# fotodiodo.net
KiCad netlist of a schematic drawn in EAGLE
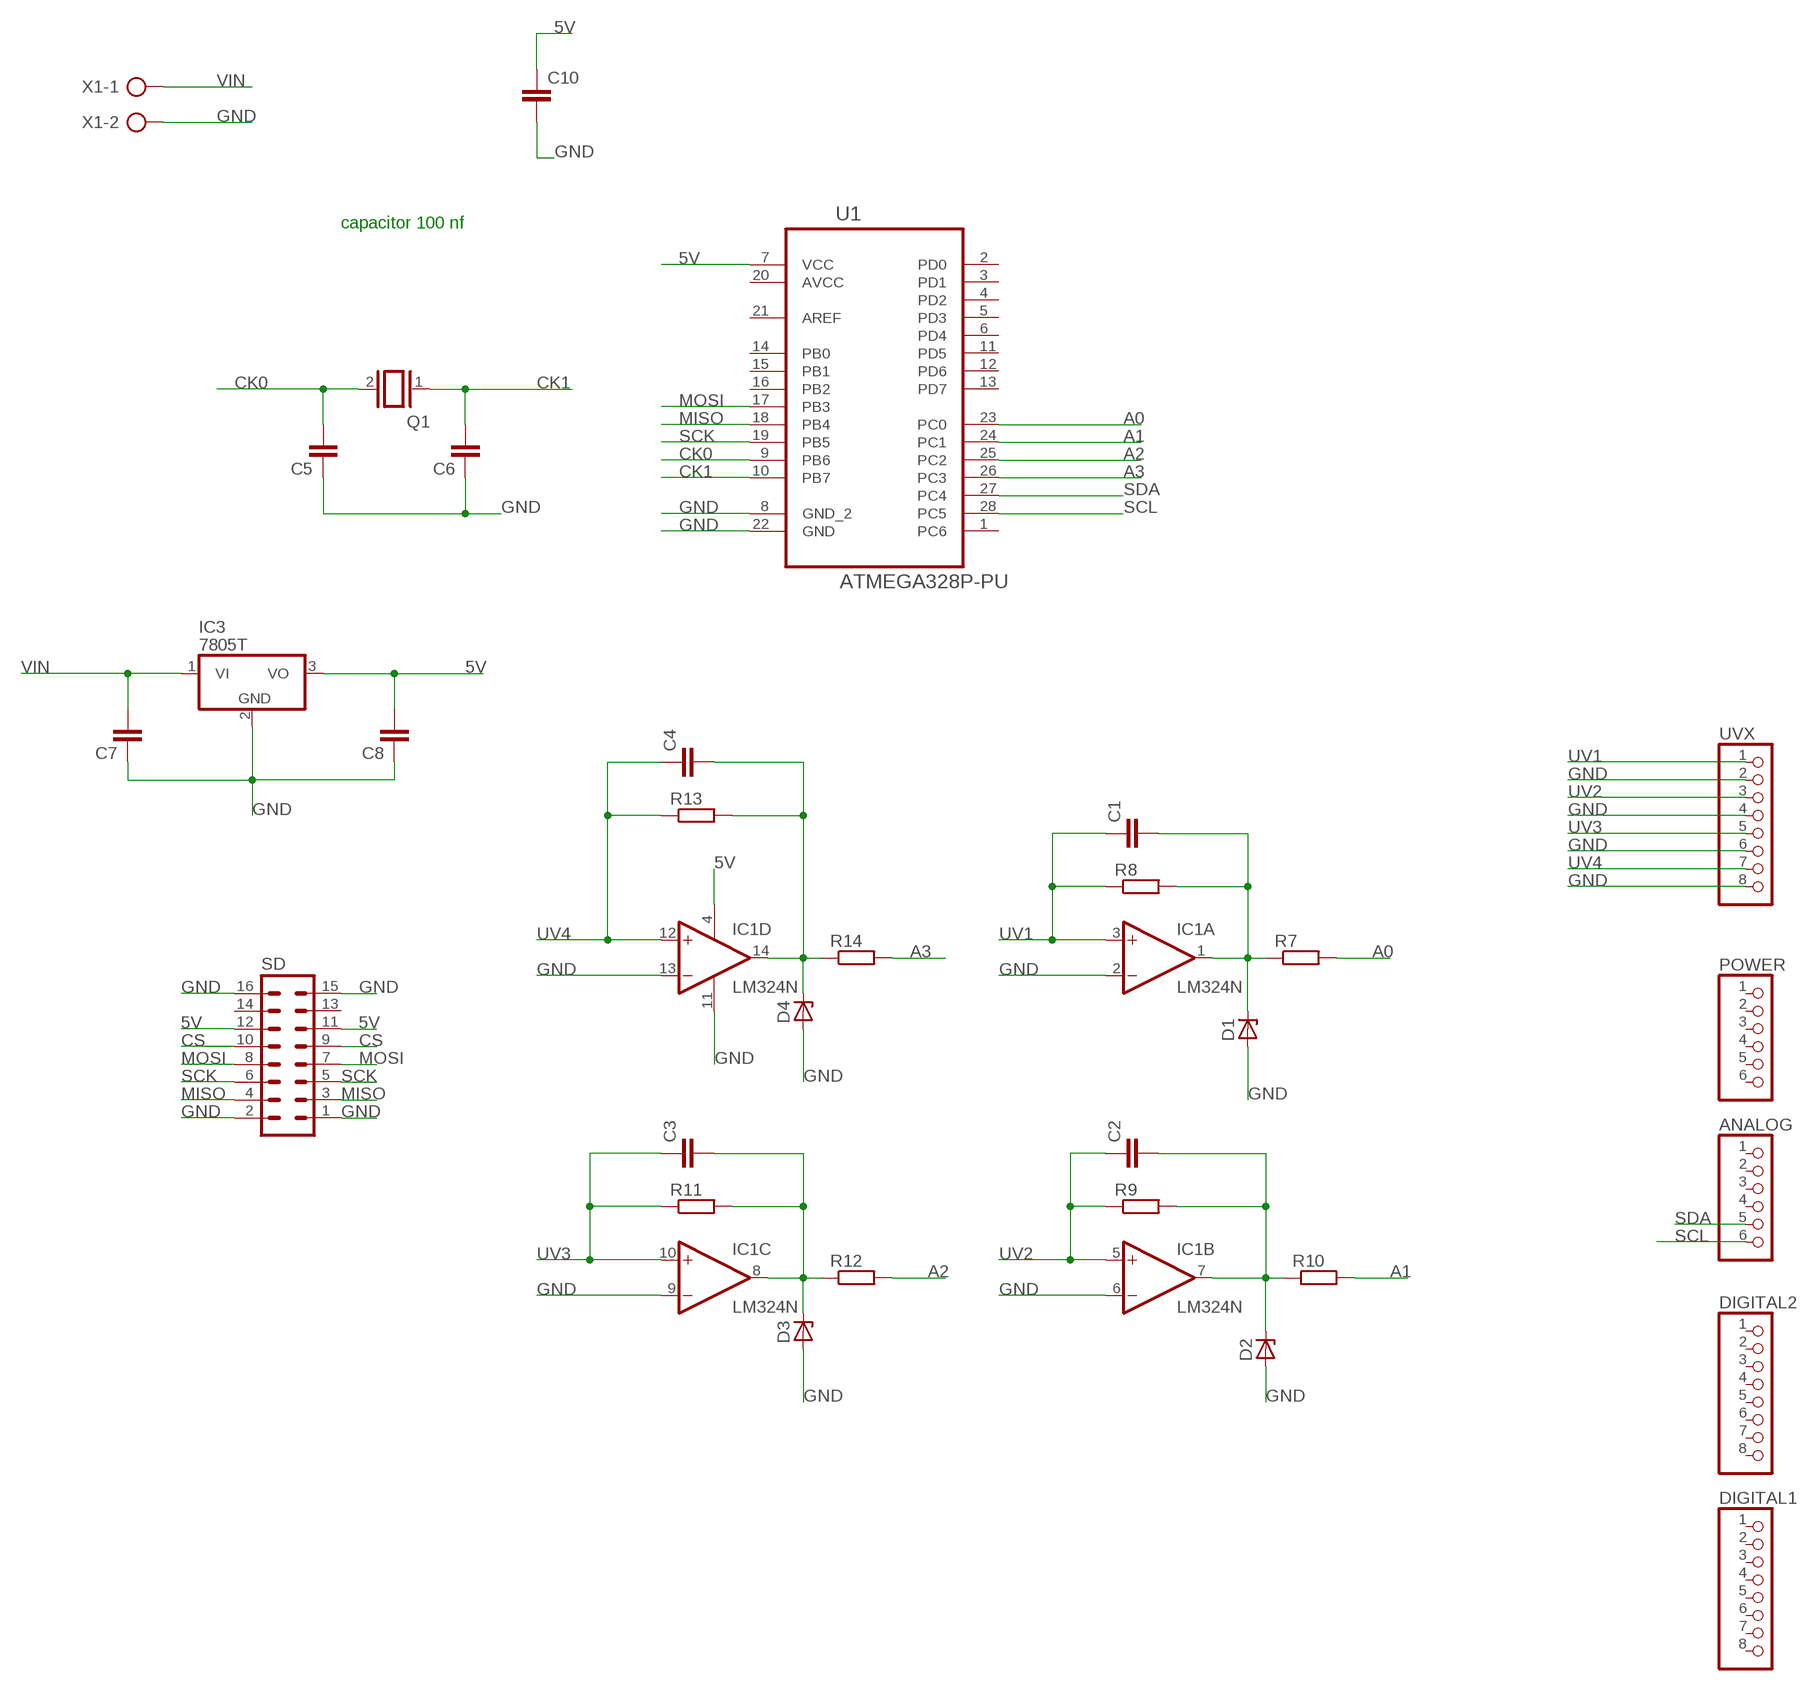
[diagram p0: schematic, sheet 1]

(export (version "E")
  (design (tool "Eeschema 10.0.6"))
  (components
    (comp (ref "ANALOG")
      (value "PINHD-1X6")
      (footprint "eagle-import:1X06")
      (libsource (lib "eagle-import") (part "PINHD-1X6"))
    )
    (comp (ref "C1")
      (value "C-EU025-025X050")
      (footprint "eagle-import:C025-025X050")
      (libsource (lib "eagle-import") (part "C-EU025-025X050"))
    )
    (comp (ref "C2")
      (value "C-EU025-025X050")
      (footprint "eagle-import:C025-025X050")
      (libsource (lib "eagle-import") (part "C-EU025-025X050"))
    )
    (comp (ref "C3")
      (value "C-EU025-025X050")
      (footprint "eagle-import:C025-025X050")
      (libsource (lib "eagle-import") (part "C-EU025-025X050"))
    )
    (comp (ref "C4")
      (value "C-EU025-025X050")
      (footprint "eagle-import:C025-025X050")
      (libsource (lib "eagle-import") (part "C-EU025-025X050"))
    )
    (comp (ref "C5")
      (value "C-EU025-025X050")
      (footprint "eagle-import:C025-025X050")
      (libsource (lib "eagle-import") (part "C-EU025-025X050"))
    )
    (comp (ref "C6")
      (value "C-EU025-025X050")
      (footprint "eagle-import:C025-025X050")
      (libsource (lib "eagle-import") (part "C-EU025-025X050"))
    )
    (comp (ref "C7")
      (value "C-EU025-025X050")
      (footprint "eagle-import:C025-025X050")
      (libsource (lib "eagle-import") (part "C-EU025-025X050"))
    )
    (comp (ref "C8")
      (value "C-EU025-025X050")
      (footprint "eagle-import:C025-025X050")
      (libsource (lib "eagle-import") (part "C-EU025-025X050"))
    )
    (comp (ref "C10")
      (value "C-EU050-055X075")
      (footprint "eagle-import:C050-055X075")
      (libsource (lib "eagle-import") (part "resistor_C-EU050-055X075"))
    )
    (comp (ref "D1")
      (value "ZENER-DIODEC1702-15")
      (footprint "eagle-import:C1702-15")
      (libsource (lib "eagle-import") (part "ZENER-DIODEC1702-15"))
    )
    (comp (ref "D2")
      (value "ZENER-DIODEC1702-15")
      (footprint "eagle-import:C1702-15")
      (libsource (lib "eagle-import") (part "ZENER-DIODEC1702-15"))
    )
    (comp (ref "D3")
      (value "ZENER-DIODEC1702-15")
      (footprint "eagle-import:C1702-15")
      (libsource (lib "eagle-import") (part "ZENER-DIODEC1702-15"))
    )
    (comp (ref "D4")
      (value "ZENER-DIODEC1702-15")
      (footprint "eagle-import:C1702-15")
      (libsource (lib "eagle-import") (part "ZENER-DIODEC1702-15"))
    )
    (comp (ref "DIGITAL1")
      (value "PINHD-1X8")
      (footprint "eagle-import:1X08")
      (libsource (lib "eagle-import") (part "PINHD-1X8"))
    )
    (comp (ref "DIGITAL2")
      (value "PINHD-1X8")
      (footprint "eagle-import:1X08")
      (libsource (lib "eagle-import") (part "PINHD-1X8"))
    )
    (comp (ref "IC1")
      (value "LM324N")
      (footprint "eagle-import:DIL14")
      (libsource (lib "eagle-import") (part "LM324N"))
    )
    (comp (ref "IC3")
      (value "7805T")
      (footprint "eagle-import:TO220H")
      (libsource (lib "eagle-import") (part "78T05"))
    )
    (comp (ref "POWER")
      (value "PINHD-1X6")
      (footprint "eagle-import:1X06")
      (libsource (lib "eagle-import") (part "PINHD-1X6"))
    )
    (comp (ref "Q1")
      (value "XTAL/S")
      (footprint "eagle-import:QS")
      (libsource (lib "eagle-import") (part "XTAL/S"))
    )
    (comp (ref "R7")
      (value "R-EU_0207/10")
      (footprint "eagle-import:0207_10")
      (libsource (lib "eagle-import") (part "R-EU_0207/10"))
    )
    (comp (ref "R8")
      (value "R-EU_0207/10")
      (footprint "eagle-import:0207_10")
      (libsource (lib "eagle-import") (part "R-EU_0207/10"))
    )
    (comp (ref "R9")
      (value "R-EU_0207/10")
      (footprint "eagle-import:0207_10")
      (libsource (lib "eagle-import") (part "R-EU_0207/10"))
    )
    (comp (ref "R10")
      (value "R-EU_0207/10")
      (footprint "eagle-import:0207_10")
      (libsource (lib "eagle-import") (part "R-EU_0207/10"))
    )
    (comp (ref "R11")
      (value "R-EU_0207/10")
      (footprint "eagle-import:0207_10")
      (libsource (lib "eagle-import") (part "R-EU_0207/10"))
    )
    (comp (ref "R12")
      (value "R-EU_0207/10")
      (footprint "eagle-import:0207_10")
      (libsource (lib "eagle-import") (part "R-EU_0207/10"))
    )
    (comp (ref "R13")
      (value "R-EU_0207/10")
      (footprint "eagle-import:0207_10")
      (libsource (lib "eagle-import") (part "R-EU_0207/10"))
    )
    (comp (ref "R14")
      (value "R-EU_0207/10")
      (footprint "eagle-import:0207_10")
      (libsource (lib "eagle-import") (part "R-EU_0207/10"))
    )
    (comp (ref "SD")
      (value "MA08-2")
      (footprint "eagle-import:MA08-2")
      (libsource (lib "eagle-import") (part "MA08-2"))
    )
    (comp (ref "U1")
      (value "ATMEGA328P-PU")
      (footprint "eagle-import:DIP254P762X457-28")
      (libsource (lib "eagle-import") (part "ATMEGA328P-PU"))
    )
    (comp (ref "UVX")
      (value "PINHD-1X8")
      (footprint "eagle-import:1X08")
      (libsource (lib "eagle-import") (part "PINHD-1X8"))
    )
    (comp (ref "X1")
      (value "AK500/2-H")
      (footprint "eagle-import:AK500_2-H")
      (libsource (lib "eagle-import") (part "AK500/2-H"))
    )
  )
  (nets
    (net (code "1") (name "/5V") (class "Default")
      (node (ref "C10") (pin "1") (pinfunction "1_1") (pintype "passive"))
      (node (ref "C8") (pin "2") (pinfunction "2_2") (pintype "passive"))
      (node (ref "IC1") (pin "4") (pinfunction "V+_4") (pintype "power_in"))
      (node (ref "IC3") (pin "3") (pinfunction "VO_3") (pintype "passive"))
      (node (ref "SD") (pin "11") (pinfunction "11_11") (pintype "passive"))
      (node (ref "SD") (pin "12") (pinfunction "12_12") (pintype "passive"))
      (node (ref "U1") (pin "7") (pinfunction "VCC_7") (pintype "power_in"))
    )
    (net (code "2") (name "/A0") (class "Default")
      (node (ref "R7") (pin "2") (pinfunction "2_2") (pintype "passive"))
      (node (ref "U1") (pin "23") (pinfunction "PC0_23") (pintype "bidirectional"))
    )
    (net (code "3") (name "/A1") (class "Default")
      (node (ref "R10") (pin "2") (pinfunction "2_2") (pintype "passive"))
      (node (ref "U1") (pin "24") (pinfunction "PC1_24") (pintype "bidirectional"))
    )
    (net (code "4") (name "/A2") (class "Default")
      (node (ref "R12") (pin "2") (pinfunction "2_2") (pintype "passive"))
      (node (ref "U1") (pin "25") (pinfunction "PC2_25") (pintype "bidirectional"))
    )
    (net (code "5") (name "/A3") (class "Default")
      (node (ref "R14") (pin "2") (pinfunction "2_2") (pintype "passive"))
      (node (ref "U1") (pin "26") (pinfunction "PC3_26") (pintype "bidirectional"))
    )
    (net (code "6") (name "/AVCC") (class "Default")
      (node (ref "U1") (pin "20") (pinfunction "AVCC_20") (pintype "power_in"))
    )
    (net (code "7") (name "/CK0") (class "Default")
      (node (ref "C5") (pin "2") (pinfunction "2_2") (pintype "passive"))
      (node (ref "Q1") (pin "2") (pinfunction "2_2") (pintype "passive"))
      (node (ref "U1") (pin "9") (pinfunction "PB6_9") (pintype "bidirectional"))
    )
    (net (code "8") (name "/CK1") (class "Default")
      (node (ref "C6") (pin "2") (pinfunction "2_2") (pintype "passive"))
      (node (ref "Q1") (pin "1") (pinfunction "1_1") (pintype "passive"))
      (node (ref "U1") (pin "10") (pinfunction "PB7_10") (pintype "bidirectional"))
    )
    (net (code "9") (name "/CS") (class "Default")
      (node (ref "SD") (pin "10") (pinfunction "10_10") (pintype "passive"))
      (node (ref "SD") (pin "9") (pinfunction "9_9") (pintype "passive"))
    )
    (net (code "10") (name "/GND") (class "Default")
      (node (ref "C10") (pin "2") (pinfunction "2_2") (pintype "passive"))
      (node (ref "C5") (pin "1") (pinfunction "1_1") (pintype "passive"))
      (node (ref "C6") (pin "1") (pinfunction "1_1") (pintype "passive"))
      (node (ref "C7") (pin "1") (pinfunction "1_1") (pintype "passive"))
      (node (ref "C8") (pin "1") (pinfunction "1_1") (pintype "passive"))
      (node (ref "D1") (pin "A") (pinfunction "A_A") (pintype "passive"))
      (node (ref "D2") (pin "A") (pinfunction "A_A") (pintype "passive"))
      (node (ref "D3") (pin "A") (pinfunction "A_A") (pintype "passive"))
      (node (ref "D4") (pin "A") (pinfunction "A_A") (pintype "passive"))
      (node (ref "IC1") (pin "11") (pinfunction "V-_11") (pintype "power_in"))
      (node (ref "IC1") (pin "13") (pinfunction "-IN_13") (pintype "input"))
      (node (ref "IC1") (pin "2") (pinfunction "-IN_2") (pintype "input"))
      (node (ref "IC1") (pin "6") (pinfunction "-IN_6") (pintype "input"))
      (node (ref "IC1") (pin "9") (pinfunction "-IN_9") (pintype "input"))
      (node (ref "IC3") (pin "2") (pinfunction "GND_2") (pintype "passive"))
      (node (ref "SD") (pin "1") (pinfunction "1_1") (pintype "passive"))
      (node (ref "SD") (pin "15") (pinfunction "15_15") (pintype "passive"))
      (node (ref "SD") (pin "16") (pinfunction "16_16") (pintype "passive"))
      (node (ref "SD") (pin "2") (pinfunction "2_2") (pintype "passive"))
      (node (ref "U1") (pin "22") (pinfunction "GND_22") (pintype "passive"))
      (node (ref "U1") (pin "8") (pinfunction "GND_2_8") (pintype "passive"))
      (node (ref "UVX") (pin "2") (pinfunction "2_2") (pintype "passive"))
      (node (ref "UVX") (pin "4") (pinfunction "4_4") (pintype "passive"))
      (node (ref "UVX") (pin "6") (pinfunction "6_6") (pintype "passive"))
      (node (ref "UVX") (pin "8") (pinfunction "8_8") (pintype "passive"))
      (node (ref "X1") (pin "2") (pinfunction "KL_2") (pintype "passive"))
    )
    (net (code "11") (name "/MISO") (class "Default")
      (node (ref "SD") (pin "3") (pinfunction "3_3") (pintype "passive"))
      (node (ref "SD") (pin "4") (pinfunction "4_4") (pintype "passive"))
      (node (ref "U1") (pin "18") (pinfunction "PB4_18") (pintype "bidirectional"))
    )
    (net (code "12") (name "/MOSI") (class "Default")
      (node (ref "SD") (pin "7") (pinfunction "7_7") (pintype "passive"))
      (node (ref "SD") (pin "8") (pinfunction "8_8") (pintype "passive"))
      (node (ref "U1") (pin "17") (pinfunction "PB3_17") (pintype "bidirectional"))
    )
    (net (code "13") (name "/SCK") (class "Default")
      (node (ref "SD") (pin "5") (pinfunction "5_5") (pintype "passive"))
      (node (ref "SD") (pin "6") (pinfunction "6_6") (pintype "passive"))
      (node (ref "U1") (pin "19") (pinfunction "PB5_19") (pintype "bidirectional"))
    )
    (net (code "14") (name "/SCL") (class "Default")
      (node (ref "ANALOG") (pin "6") (pinfunction "6_6") (pintype "passive"))
      (node (ref "U1") (pin "28") (pinfunction "PC5_28") (pintype "bidirectional"))
    )
    (net (code "15") (name "/SDA") (class "Default")
      (node (ref "ANALOG") (pin "5") (pinfunction "5_5") (pintype "passive"))
      (node (ref "U1") (pin "27") (pinfunction "PC4_27") (pintype "bidirectional"))
    )
    (net (code "16") (name "/UV1") (class "Default")
      (node (ref "C1") (pin "1") (pinfunction "1_1") (pintype "passive"))
      (node (ref "IC1") (pin "3") (pinfunction "+IN_3") (pintype "input"))
      (node (ref "R8") (pin "1") (pinfunction "1_1") (pintype "passive"))
      (node (ref "UVX") (pin "1") (pinfunction "1_1") (pintype "passive"))
    )
    (net (code "17") (name "/UV2") (class "Default")
      (node (ref "C2") (pin "1") (pinfunction "1_1") (pintype "passive"))
      (node (ref "IC1") (pin "5") (pinfunction "+IN_5") (pintype "input"))
      (node (ref "R9") (pin "1") (pinfunction "1_1") (pintype "passive"))
      (node (ref "UVX") (pin "3") (pinfunction "3_3") (pintype "passive"))
    )
    (net (code "18") (name "/UV3") (class "Default")
      (node (ref "C3") (pin "1") (pinfunction "1_1") (pintype "passive"))
      (node (ref "IC1") (pin "10") (pinfunction "+IN_10") (pintype "input"))
      (node (ref "R11") (pin "1") (pinfunction "1_1") (pintype "passive"))
      (node (ref "UVX") (pin "5") (pinfunction "5_5") (pintype "passive"))
    )
    (net (code "19") (name "/UV4") (class "Default")
      (node (ref "C4") (pin "1") (pinfunction "1_1") (pintype "passive"))
      (node (ref "IC1") (pin "12") (pinfunction "+IN_12") (pintype "input"))
      (node (ref "R13") (pin "1") (pinfunction "1_1") (pintype "passive"))
      (node (ref "UVX") (pin "7") (pinfunction "7_7") (pintype "passive"))
    )
    (net (code "20") (name "/VIN") (class "Default")
      (node (ref "C7") (pin "2") (pinfunction "2_2") (pintype "passive"))
      (node (ref "IC3") (pin "1") (pinfunction "VI_1") (pintype "input"))
      (node (ref "X1") (pin "1") (pinfunction "KL_1") (pintype "passive"))
    )
    (net (code "21") (name "Net-(IC1A-OUT)") (class "Default")
      (node (ref "C1") (pin "2") (pinfunction "2_2") (pintype "passive"))
      (node (ref "D1") (pin "C") (pinfunction "C_C") (pintype "passive"))
      (node (ref "IC1") (pin "1") (pinfunction "OUT_1") (pintype "output"))
      (node (ref "R7") (pin "1") (pinfunction "1_1") (pintype "passive"))
      (node (ref "R8") (pin "2") (pinfunction "2_2") (pintype "passive"))
    )
    (net (code "22") (name "Net-(IC1B-OUT)") (class "Default")
      (node (ref "C2") (pin "2") (pinfunction "2_2") (pintype "passive"))
      (node (ref "D2") (pin "C") (pinfunction "C_C") (pintype "passive"))
      (node (ref "IC1") (pin "7") (pinfunction "OUT_7") (pintype "output"))
      (node (ref "R10") (pin "1") (pinfunction "1_1") (pintype "passive"))
      (node (ref "R9") (pin "2") (pinfunction "2_2") (pintype "passive"))
    )
    (net (code "23") (name "Net-(IC1C-OUT)") (class "Default")
      (node (ref "C3") (pin "2") (pinfunction "2_2") (pintype "passive"))
      (node (ref "D3") (pin "C") (pinfunction "C_C") (pintype "passive"))
      (node (ref "IC1") (pin "8") (pinfunction "OUT_8") (pintype "output"))
      (node (ref "R11") (pin "2") (pinfunction "2_2") (pintype "passive"))
      (node (ref "R12") (pin "1") (pinfunction "1_1") (pintype "passive"))
    )
    (net (code "24") (name "Net-(IC1D-OUT)") (class "Default")
      (node (ref "C4") (pin "2") (pinfunction "2_2") (pintype "passive"))
      (node (ref "D4") (pin "C") (pinfunction "C_C") (pintype "passive"))
      (node (ref "IC1") (pin "14") (pinfunction "OUT_14") (pintype "output"))
      (node (ref "R13") (pin "2") (pinfunction "2_2") (pintype "passive"))
      (node (ref "R14") (pin "1") (pinfunction "1_1") (pintype "passive"))
    )
    (net (code "25") (name "unconnected-(ANALOG-Pad1)") (class "Default")
      (node (ref "ANALOG") (pin "1") (pinfunction "1_1") (pintype "passive"))
    )
    (net (code "26") (name "unconnected-(ANALOG-Pad2)") (class "Default")
      (node (ref "ANALOG") (pin "2") (pinfunction "2_2") (pintype "passive"))
    )
    (net (code "27") (name "unconnected-(ANALOG-Pad3)") (class "Default")
      (node (ref "ANALOG") (pin "3") (pinfunction "3_3") (pintype "passive"))
    )
    (net (code "28") (name "unconnected-(ANALOG-Pad4)") (class "Default")
      (node (ref "ANALOG") (pin "4") (pinfunction "4_4") (pintype "passive"))
    )
    (net (code "29") (name "unconnected-(DIGITAL1-Pad1)") (class "Default")
      (node (ref "DIGITAL1") (pin "1") (pinfunction "1_1") (pintype "passive"))
    )
    (net (code "30") (name "unconnected-(DIGITAL1-Pad2)") (class "Default")
      (node (ref "DIGITAL1") (pin "2") (pinfunction "2_2") (pintype "passive"))
    )
    (net (code "31") (name "unconnected-(DIGITAL1-Pad3)") (class "Default")
      (node (ref "DIGITAL1") (pin "3") (pinfunction "3_3") (pintype "passive"))
    )
    (net (code "32") (name "unconnected-(DIGITAL1-Pad4)") (class "Default")
      (node (ref "DIGITAL1") (pin "4") (pinfunction "4_4") (pintype "passive"))
    )
    (net (code "33") (name "unconnected-(DIGITAL1-Pad5)") (class "Default")
      (node (ref "DIGITAL1") (pin "5") (pinfunction "5_5") (pintype "passive"))
    )
    (net (code "34") (name "unconnected-(DIGITAL1-Pad6)") (class "Default")
      (node (ref "DIGITAL1") (pin "6") (pinfunction "6_6") (pintype "passive"))
    )
    (net (code "35") (name "unconnected-(DIGITAL1-Pad7)") (class "Default")
      (node (ref "DIGITAL1") (pin "7") (pinfunction "7_7") (pintype "passive"))
    )
    (net (code "36") (name "unconnected-(DIGITAL1-Pad8)") (class "Default")
      (node (ref "DIGITAL1") (pin "8") (pinfunction "8_8") (pintype "passive"))
    )
    (net (code "37") (name "unconnected-(DIGITAL2-Pad1)") (class "Default")
      (node (ref "DIGITAL2") (pin "1") (pinfunction "1_1") (pintype "passive"))
    )
    (net (code "38") (name "unconnected-(DIGITAL2-Pad2)") (class "Default")
      (node (ref "DIGITAL2") (pin "2") (pinfunction "2_2") (pintype "passive"))
    )
    (net (code "39") (name "unconnected-(DIGITAL2-Pad3)") (class "Default")
      (node (ref "DIGITAL2") (pin "3") (pinfunction "3_3") (pintype "passive"))
    )
    (net (code "40") (name "unconnected-(DIGITAL2-Pad4)") (class "Default")
      (node (ref "DIGITAL2") (pin "4") (pinfunction "4_4") (pintype "passive"))
    )
    (net (code "41") (name "unconnected-(DIGITAL2-Pad5)") (class "Default")
      (node (ref "DIGITAL2") (pin "5") (pinfunction "5_5") (pintype "passive"))
    )
    (net (code "42") (name "unconnected-(DIGITAL2-Pad6)") (class "Default")
      (node (ref "DIGITAL2") (pin "6") (pinfunction "6_6") (pintype "passive"))
    )
    (net (code "43") (name "unconnected-(DIGITAL2-Pad7)") (class "Default")
      (node (ref "DIGITAL2") (pin "7") (pinfunction "7_7") (pintype "passive"))
    )
    (net (code "44") (name "unconnected-(DIGITAL2-Pad8)") (class "Default")
      (node (ref "DIGITAL2") (pin "8") (pinfunction "8_8") (pintype "passive"))
    )
    (net (code "45") (name "unconnected-(POWER-Pad1)") (class "Default")
      (node (ref "POWER") (pin "1") (pinfunction "1_1") (pintype "passive"))
    )
    (net (code "46") (name "unconnected-(POWER-Pad2)") (class "Default")
      (node (ref "POWER") (pin "2") (pinfunction "2_2") (pintype "passive"))
    )
    (net (code "47") (name "unconnected-(POWER-Pad3)") (class "Default")
      (node (ref "POWER") (pin "3") (pinfunction "3_3") (pintype "passive"))
    )
    (net (code "48") (name "unconnected-(POWER-Pad4)") (class "Default")
      (node (ref "POWER") (pin "4") (pinfunction "4_4") (pintype "passive"))
    )
    (net (code "49") (name "unconnected-(POWER-Pad5)") (class "Default")
      (node (ref "POWER") (pin "5") (pinfunction "5_5") (pintype "passive"))
    )
    (net (code "50") (name "unconnected-(POWER-Pad6)") (class "Default")
      (node (ref "POWER") (pin "6") (pinfunction "6_6") (pintype "passive"))
    )
    (net (code "51") (name "unconnected-(SD-Pad13)") (class "Default")
      (node (ref "SD") (pin "13") (pinfunction "13_13") (pintype "passive"))
    )
    (net (code "52") (name "unconnected-(SD-Pad14)") (class "Default")
      (node (ref "SD") (pin "14") (pinfunction "14_14") (pintype "passive"))
    )
    (net (code "53") (name "unconnected-(U1-AREF-Pad21)") (class "Default")
      (node (ref "U1") (pin "21") (pinfunction "AREF_21") (pintype "input"))
    )
    (net (code "54") (name "unconnected-(U1-PB0-Pad14)") (class "Default")
      (node (ref "U1") (pin "14") (pinfunction "PB0_14") (pintype "bidirectional"))
    )
    (net (code "55") (name "unconnected-(U1-PB1-Pad15)") (class "Default")
      (node (ref "U1") (pin "15") (pinfunction "PB1_15") (pintype "bidirectional"))
    )
    (net (code "56") (name "unconnected-(U1-PB2-Pad16)") (class "Default")
      (node (ref "U1") (pin "16") (pinfunction "PB2_16") (pintype "bidirectional"))
    )
    (net (code "57") (name "unconnected-(U1-PC6-Pad1)") (class "Default")
      (node (ref "U1") (pin "1") (pinfunction "PC6_1") (pintype "bidirectional"))
    )
    (net (code "58") (name "unconnected-(U1-PD0-Pad2)") (class "Default")
      (node (ref "U1") (pin "2") (pinfunction "PD0_2") (pintype "bidirectional"))
    )
    (net (code "59") (name "unconnected-(U1-PD1-Pad3)") (class "Default")
      (node (ref "U1") (pin "3") (pinfunction "PD1_3") (pintype "bidirectional"))
    )
    (net (code "60") (name "unconnected-(U1-PD2-Pad4)") (class "Default")
      (node (ref "U1") (pin "4") (pinfunction "PD2_4") (pintype "bidirectional"))
    )
    (net (code "61") (name "unconnected-(U1-PD3-Pad5)") (class "Default")
      (node (ref "U1") (pin "5") (pinfunction "PD3_5") (pintype "bidirectional"))
    )
    (net (code "62") (name "unconnected-(U1-PD4-Pad6)") (class "Default")
      (node (ref "U1") (pin "6") (pinfunction "PD4_6") (pintype "bidirectional"))
    )
    (net (code "63") (name "unconnected-(U1-PD5-Pad11)") (class "Default")
      (node (ref "U1") (pin "11") (pinfunction "PD5_11") (pintype "bidirectional"))
    )
    (net (code "64") (name "unconnected-(U1-PD6-Pad12)") (class "Default")
      (node (ref "U1") (pin "12") (pinfunction "PD6_12") (pintype "bidirectional"))
    )
    (net (code "65") (name "unconnected-(U1-PD7-Pad13)") (class "Default")
      (node (ref "U1") (pin "13") (pinfunction "PD7_13") (pintype "bidirectional"))
    )
  )
)
